# RF_Test_Board.net
KiCad netlist of a schematic drawn in EAGLE
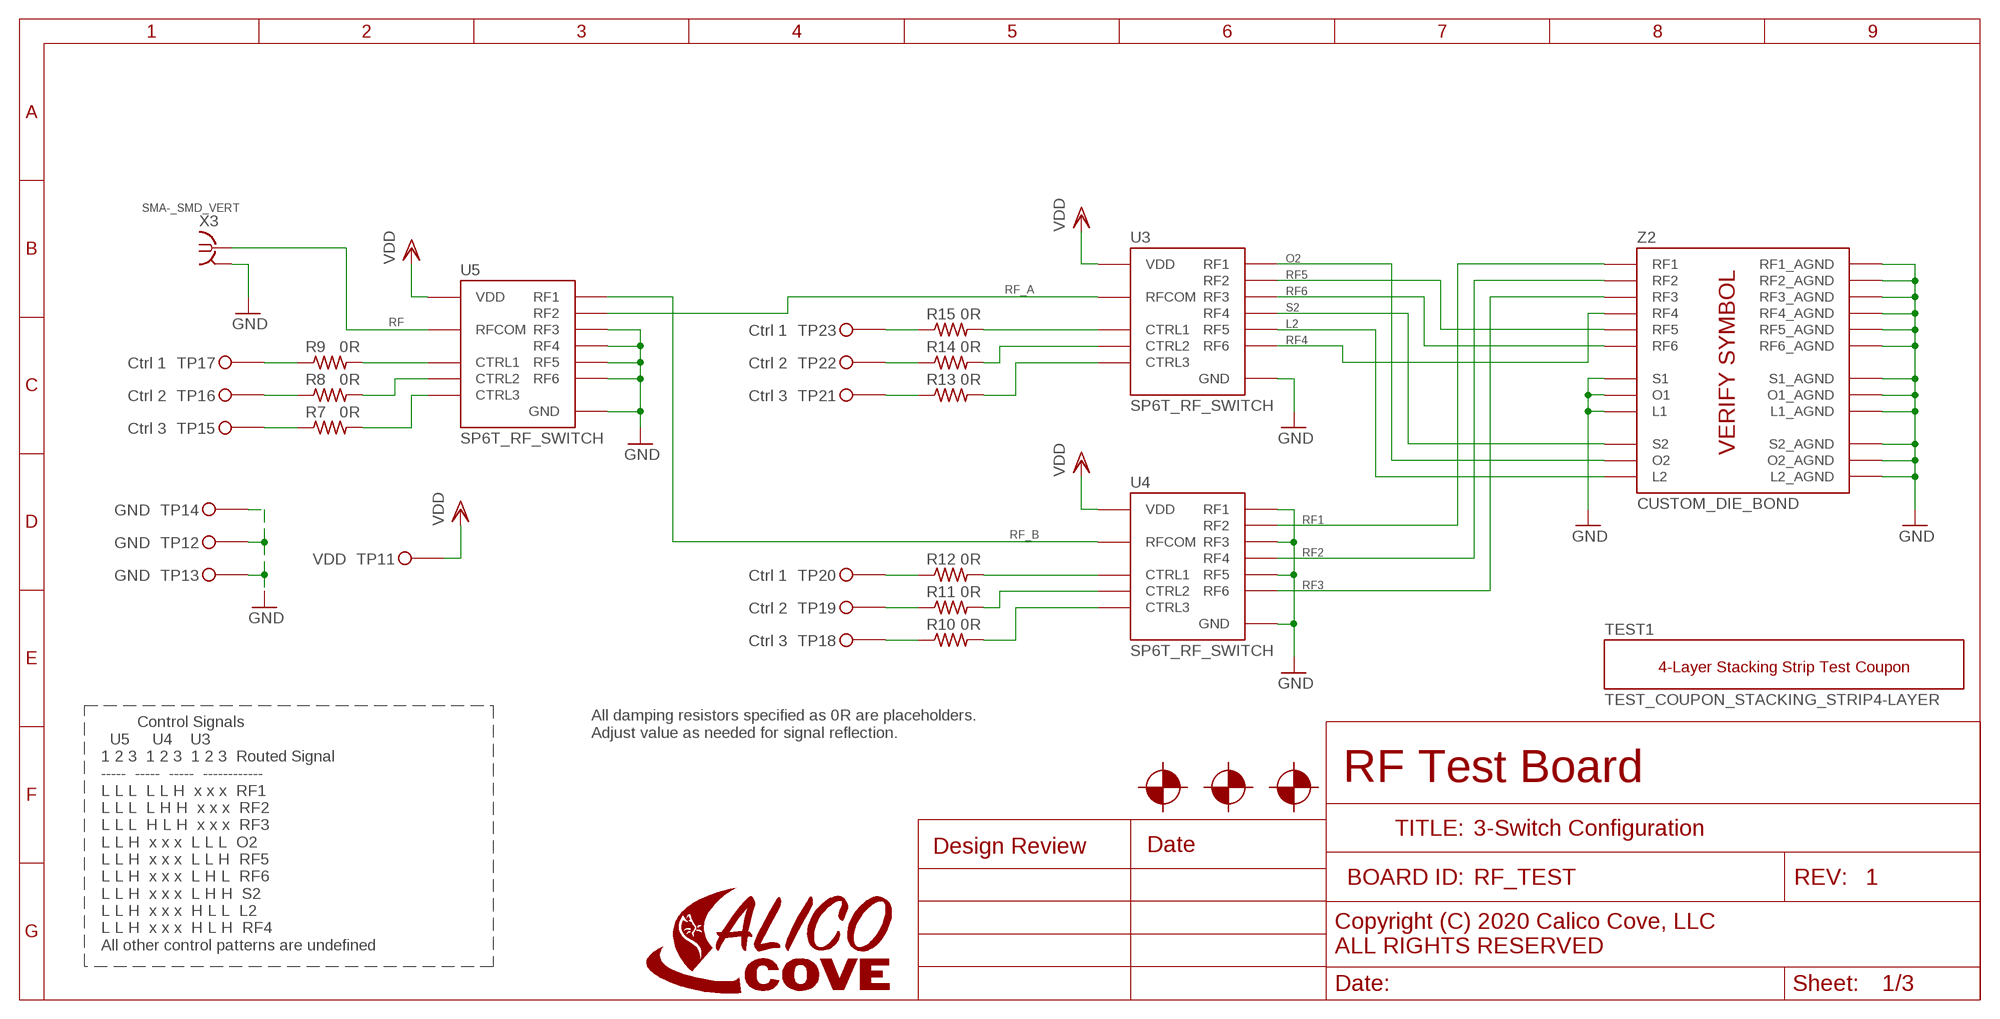
[diagram p0: schematic, sheet 1]
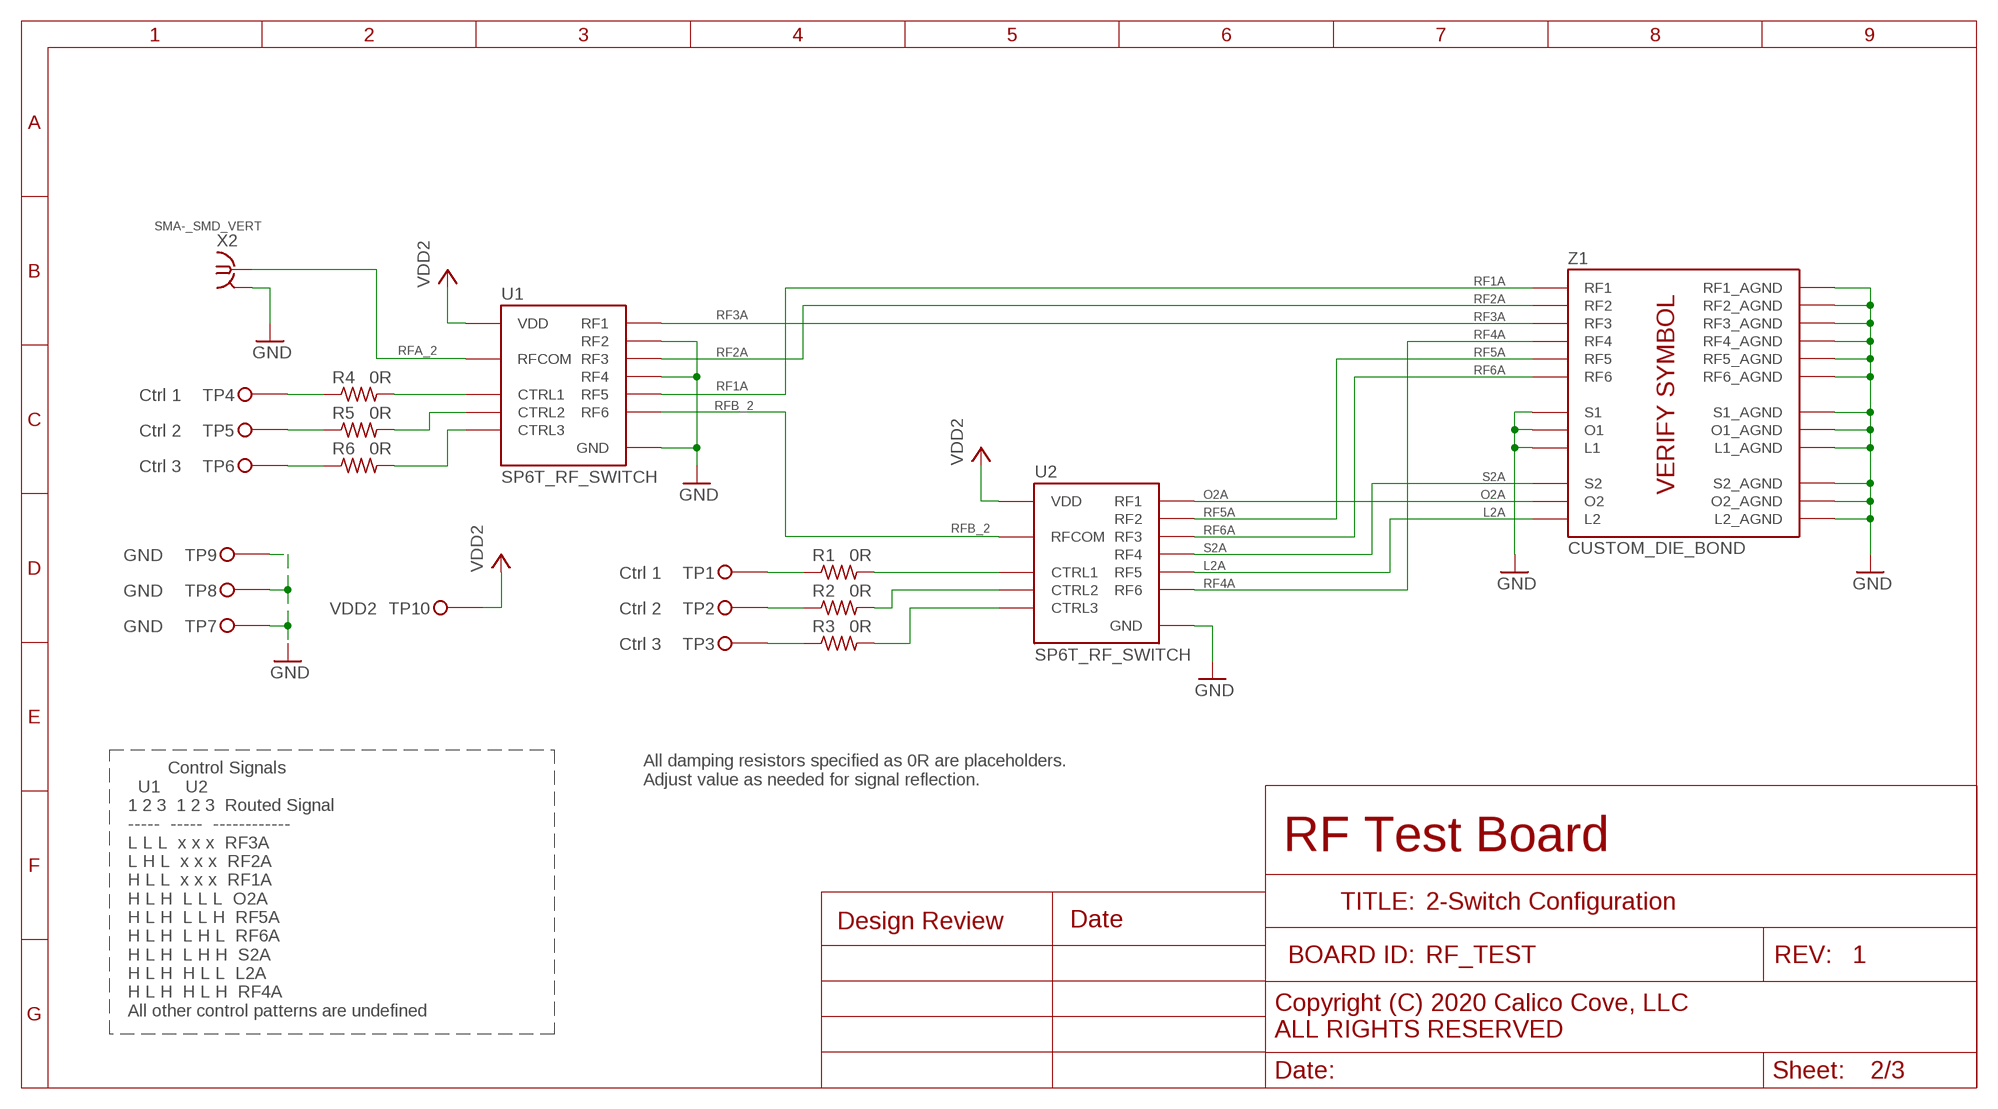
[diagram p1: schematic, sheet 2]
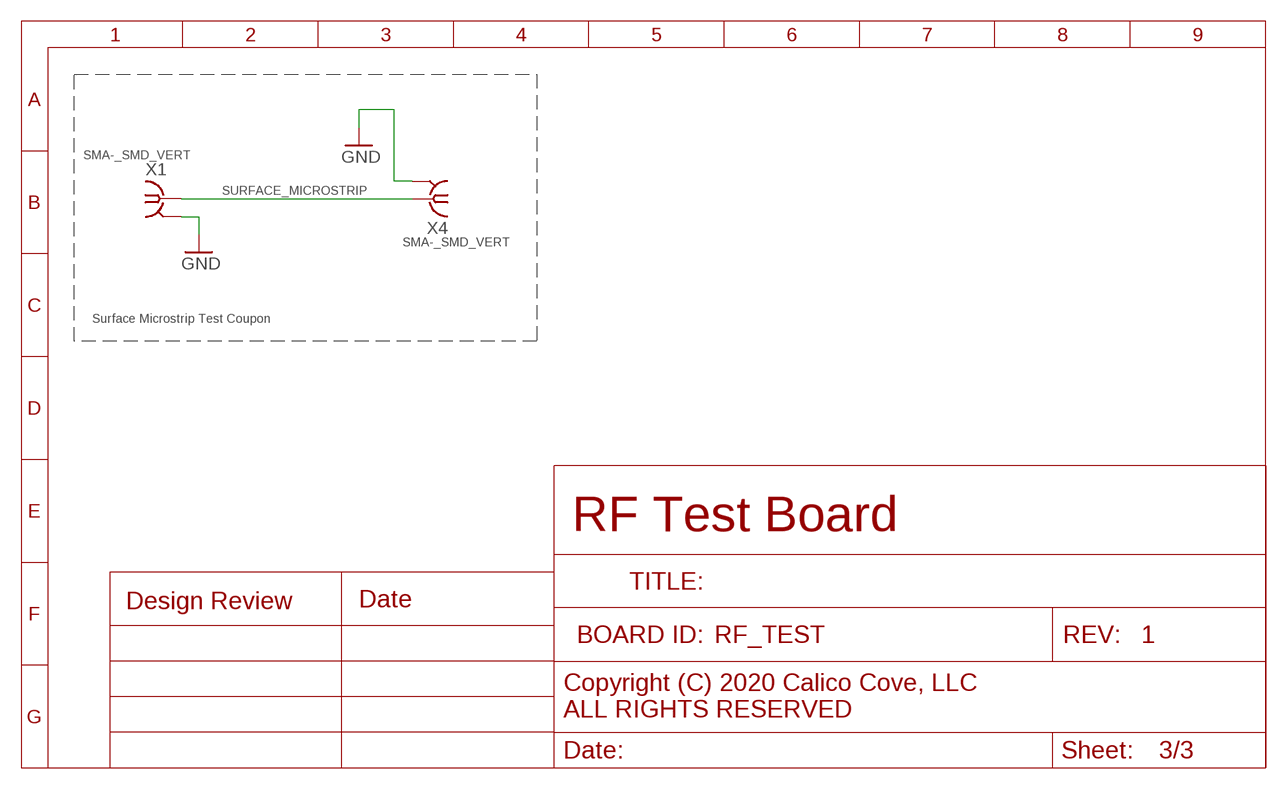
[diagram p2: schematic, sheet 3]

(export (version "E")
  (design (tool "Eeschema 10.0.6"))
  (components
    (comp (ref "X1")
      (value "SMA-_SMD_VERT")
      (footprint "eagle-import:LINX_SMD")
      (fields (field (name "MFG") "Linx Technologies, Inc.") (field (name "MPN") "CONSMA001-SMD-G"))
      (libsource (lib "eagle-import") (part "SMA-_SMD_VERT"))
    )
    (comp (ref "X4")
      (value "SMA-_SMD_VERT")
      (footprint "eagle-import:LINX_SMD")
      (fields (field (name "MFG") "Linx Technologies, Inc.") (field (name "MPN") "CONSMA001-SMD-G"))
      (libsource (lib "eagle-import") (part "SMA-_SMD_VERT"))
    )
    (comp (ref "R1")
      (value "0R")
      (footprint "eagle-import:0603")
      (libsource (lib "eagle-import") (part "RESISTOR0603"))
    )
    (comp (ref "R2")
      (value "0R")
      (footprint "eagle-import:0603")
      (libsource (lib "eagle-import") (part "RESISTOR0603"))
    )
    (comp (ref "R3")
      (value "0R")
      (footprint "eagle-import:0603")
      (libsource (lib "eagle-import") (part "RESISTOR0603"))
    )
    (comp (ref "R4")
      (value "0R")
      (footprint "eagle-import:0603")
      (libsource (lib "eagle-import") (part "RESISTOR0603"))
    )
    (comp (ref "R5")
      (value "0R")
      (footprint "eagle-import:0603")
      (libsource (lib "eagle-import") (part "RESISTOR0603"))
    )
    (comp (ref "R6")
      (value "0R")
      (footprint "eagle-import:0603")
      (libsource (lib "eagle-import") (part "RESISTOR0603"))
    )
    (comp (ref "TP1")
      (value "Ctrl 1")
      (footprint "eagle-import:TEST_POINT_TH")
      (libsource (lib "eagle-import") (part "TEST_POINT_TH"))
    )
    (comp (ref "TP2")
      (value "Ctrl 2")
      (footprint "eagle-import:TEST_POINT_TH")
      (libsource (lib "eagle-import") (part "TEST_POINT_TH"))
    )
    (comp (ref "TP3")
      (value "Ctrl 3")
      (footprint "eagle-import:TEST_POINT_TH")
      (libsource (lib "eagle-import") (part "TEST_POINT_TH"))
    )
    (comp (ref "TP4")
      (value "Ctrl 1")
      (footprint "eagle-import:TEST_POINT_TH")
      (libsource (lib "eagle-import") (part "TEST_POINT_TH"))
    )
    (comp (ref "TP5")
      (value "Ctrl 2")
      (footprint "eagle-import:TEST_POINT_TH")
      (libsource (lib "eagle-import") (part "TEST_POINT_TH"))
    )
    (comp (ref "TP6")
      (value "Ctrl 3")
      (footprint "eagle-import:TEST_POINT_TH")
      (libsource (lib "eagle-import") (part "TEST_POINT_TH"))
    )
    (comp (ref "TP7")
      (value "GND")
      (footprint "eagle-import:TEST_POINT_TH")
      (libsource (lib "eagle-import") (part "TEST_POINT_TH"))
    )
    (comp (ref "TP8")
      (value "GND")
      (footprint "eagle-import:TEST_POINT_TH")
      (libsource (lib "eagle-import") (part "TEST_POINT_TH"))
    )
    (comp (ref "TP9")
      (value "GND")
      (footprint "eagle-import:TEST_POINT_TH")
      (libsource (lib "eagle-import") (part "TEST_POINT_TH"))
    )
    (comp (ref "TP10")
      (value "VDD2")
      (footprint "eagle-import:TEST_POINT_TH")
      (libsource (lib "eagle-import") (part "TEST_POINT_TH"))
    )
    (comp (ref "U1")
      (value "SP6T_RF_SWITCH")
      (footprint "eagle-import:MT1817")
      (libsource (lib "eagle-import") (part "SP6T_RF_SWITCH"))
    )
    (comp (ref "U2")
      (value "SP6T_RF_SWITCH")
      (footprint "eagle-import:MT1817")
      (libsource (lib "eagle-import") (part "SP6T_RF_SWITCH"))
    )
    (comp (ref "X2")
      (value "SMA-_SMD_VERT")
      (footprint "eagle-import:LINX_SMD")
      (fields (field (name "MFG") "Linx Technologies, Inc.") (field (name "MPN") "CONSMA001-SMD-G"))
      (libsource (lib "eagle-import") (part "SMA-_SMD_VERT"))
    )
    (comp (ref "Z1")
      (value "CUSTOM_DIE_BOND")
      (footprint "eagle-import:CUSTOM_IC_DIE_BOND")
      (libsource (lib "eagle-import") (part "CUSTOM_DIE_BOND"))
    )
    (comp (ref "DOCBLOCK1")
      (value "DOCBLOCK_REVIEW_2020")
      (footprint "eagle-import:DOCBLOCK")
      (libsource (lib "eagle-import") (part "DOCBLOCK_REVIEW_2020"))
    )
    (comp (ref "FID$1")
      (value "FIDUCIAL")
      (footprint "eagle-import:FIDUCIAL")
      (libsource (lib "eagle-import") (part "FIDUCIAL"))
    )
    (comp (ref "FID$2")
      (value "FIDUCIAL")
      (footprint "eagle-import:FIDUCIAL")
      (libsource (lib "eagle-import") (part "FIDUCIAL"))
    )
    (comp (ref "FID$3")
      (value "FIDUCIAL")
      (footprint "eagle-import:FIDUCIAL")
      (libsource (lib "eagle-import") (part "FIDUCIAL"))
    )
    (comp (ref "LOGO1")
      (value "LOGO_CC_SMALL")
      (footprint "eagle-import:CC_FULL_SMALL")
      (libsource (lib "eagle-import") (part "LOGO_CC_SMALL"))
    )
    (comp (ref "R7")
      (value "0R")
      (footprint "eagle-import:0603")
      (libsource (lib "eagle-import") (part "RESISTOR0603"))
    )
    (comp (ref "R8")
      (value "0R")
      (footprint "eagle-import:0603")
      (libsource (lib "eagle-import") (part "RESISTOR0603"))
    )
    (comp (ref "R9")
      (value "0R")
      (footprint "eagle-import:0603")
      (libsource (lib "eagle-import") (part "RESISTOR0603"))
    )
    (comp (ref "R10")
      (value "0R")
      (footprint "eagle-import:0603")
      (libsource (lib "eagle-import") (part "RESISTOR0603"))
    )
    (comp (ref "R11")
      (value "0R")
      (footprint "eagle-import:0603")
      (libsource (lib "eagle-import") (part "RESISTOR0603"))
    )
    (comp (ref "R12")
      (value "0R")
      (footprint "eagle-import:0603")
      (libsource (lib "eagle-import") (part "RESISTOR0603"))
    )
    (comp (ref "R13")
      (value "0R")
      (footprint "eagle-import:0603")
      (libsource (lib "eagle-import") (part "RESISTOR0603"))
    )
    (comp (ref "R14")
      (value "0R")
      (footprint "eagle-import:0603")
      (libsource (lib "eagle-import") (part "RESISTOR0603"))
    )
    (comp (ref "R15")
      (value "0R")
      (footprint "eagle-import:0603")
      (libsource (lib "eagle-import") (part "RESISTOR0603"))
    )
    (comp (ref "TEST1")
      (value "TEST_COUPON_STACKING_STRIP4-LAYER")
      (footprint "eagle-import:TEST_COUPON_4-LAYER_STACKING_STRIP")
      (libsource (lib "eagle-import") (part "TEST_COUPON_STACKING_STRIP4-LAYER"))
    )
    (comp (ref "TP11")
      (value "VDD")
      (footprint "eagle-import:TEST_POINT_TH")
      (libsource (lib "eagle-import") (part "TEST_POINT_TH"))
    )
    (comp (ref "TP12")
      (value "GND")
      (footprint "eagle-import:TEST_POINT_TH")
      (libsource (lib "eagle-import") (part "TEST_POINT_TH"))
    )
    (comp (ref "TP13")
      (value "GND")
      (footprint "eagle-import:TEST_POINT_TH")
      (libsource (lib "eagle-import") (part "TEST_POINT_TH"))
    )
    (comp (ref "TP14")
      (value "GND")
      (footprint "eagle-import:TEST_POINT_TH")
      (libsource (lib "eagle-import") (part "TEST_POINT_TH"))
    )
    (comp (ref "TP15")
      (value "Ctrl 3")
      (footprint "eagle-import:TEST_POINT_TH")
      (libsource (lib "eagle-import") (part "TEST_POINT_TH"))
    )
    (comp (ref "TP16")
      (value "Ctrl 2")
      (footprint "eagle-import:TEST_POINT_TH")
      (libsource (lib "eagle-import") (part "TEST_POINT_TH"))
    )
    (comp (ref "TP17")
      (value "Ctrl 1")
      (footprint "eagle-import:TEST_POINT_TH")
      (libsource (lib "eagle-import") (part "TEST_POINT_TH"))
    )
    (comp (ref "TP18")
      (value "Ctrl 3")
      (footprint "eagle-import:TEST_POINT_TH")
      (libsource (lib "eagle-import") (part "TEST_POINT_TH"))
    )
    (comp (ref "TP19")
      (value "Ctrl 2")
      (footprint "eagle-import:TEST_POINT_TH")
      (libsource (lib "eagle-import") (part "TEST_POINT_TH"))
    )
    (comp (ref "TP20")
      (value "Ctrl 1")
      (footprint "eagle-import:TEST_POINT_TH")
      (libsource (lib "eagle-import") (part "TEST_POINT_TH"))
    )
    (comp (ref "TP21")
      (value "Ctrl 3")
      (footprint "eagle-import:TEST_POINT_TH")
      (libsource (lib "eagle-import") (part "TEST_POINT_TH"))
    )
    (comp (ref "TP22")
      (value "Ctrl 2")
      (footprint "eagle-import:TEST_POINT_TH")
      (libsource (lib "eagle-import") (part "TEST_POINT_TH"))
    )
    (comp (ref "TP23")
      (value "Ctrl 1")
      (footprint "eagle-import:TEST_POINT_TH")
      (libsource (lib "eagle-import") (part "TEST_POINT_TH"))
    )
    (comp (ref "U3")
      (value "SP6T_RF_SWITCH")
      (footprint "eagle-import:MT1817")
      (libsource (lib "eagle-import") (part "SP6T_RF_SWITCH"))
    )
    (comp (ref "U4")
      (value "SP6T_RF_SWITCH")
      (footprint "eagle-import:MT1817")
      (libsource (lib "eagle-import") (part "SP6T_RF_SWITCH"))
    )
    (comp (ref "U5")
      (value "SP6T_RF_SWITCH")
      (footprint "eagle-import:MT1817")
      (libsource (lib "eagle-import") (part "SP6T_RF_SWITCH"))
    )
    (comp (ref "X3")
      (value "SMA-_SMD_VERT")
      (footprint "eagle-import:LINX_SMD")
      (fields (field (name "MFG") "Linx Technologies, Inc.") (field (name "MPN") "CONSMA001-SMD-G"))
      (libsource (lib "eagle-import") (part "SMA-_SMD_VERT"))
    )
    (comp (ref "Z2")
      (value "CUSTOM_DIE_BOND")
      (footprint "eagle-import:CUSTOM_IC_DIE_BOND")
      (libsource (lib "eagle-import") (part "CUSTOM_DIE_BOND"))
    )
  )
  (nets
    (net (code "1") (name "GND") (class "Default")
      (node (ref "TP12") (pin "P$1") (pinfunction "P$1_P$1") (pintype "passive"))
      (node (ref "TP13") (pin "P$1") (pinfunction "P$1_P$1") (pintype "passive"))
      (node (ref "TP14") (pin "P$1") (pinfunction "P$1_P$1") (pintype "passive"))
      (node (ref "TP7") (pin "P$1") (pinfunction "P$1_P$1") (pintype "passive"))
      (node (ref "TP8") (pin "P$1") (pinfunction "P$1_P$1") (pintype "passive"))
      (node (ref "TP9") (pin "P$1") (pinfunction "P$1_P$1") (pintype "passive"))
      (node (ref "U1") (pin "10") (pinfunction "RF4_10") (pintype "passive"))
      (node (ref "U1") (pin "9") (pinfunction "RF2_9") (pintype "passive"))
      (node (ref "U1") (pin "PAD") (pinfunction "GND_PAD") (pintype "power_in"))
      (node (ref "U1") (pin "PAD_VIA") (pinfunction "GND_PAD_VIA") (pintype "power_in"))
      (node (ref "U2") (pin "PAD") (pinfunction "GND_PAD") (pintype "power_in"))
      (node (ref "U2") (pin "PAD_VIA") (pinfunction "GND_PAD_VIA") (pintype "power_in"))
      (node (ref "U3") (pin "PAD") (pinfunction "GND_PAD") (pintype "power_in"))
      (node (ref "U3") (pin "PAD_VIA") (pinfunction "GND_PAD_VIA") (pintype "power_in"))
      (node (ref "U4") (pin "1") (pinfunction "RF5_1") (pintype "passive"))
      (node (ref "U4") (pin "2") (pinfunction "RF3_2") (pintype "passive"))
      (node (ref "U4") (pin "3") (pinfunction "RF1_3") (pintype "passive"))
      (node (ref "U4") (pin "PAD") (pinfunction "GND_PAD") (pintype "power_in"))
      (node (ref "U4") (pin "PAD_VIA") (pinfunction "GND_PAD_VIA") (pintype "power_in"))
      (node (ref "U5") (pin "1") (pinfunction "RF5_1") (pintype "passive"))
      (node (ref "U5") (pin "10") (pinfunction "RF4_10") (pintype "passive"))
      (node (ref "U5") (pin "11") (pinfunction "RF6_11") (pintype "passive"))
      (node (ref "U5") (pin "2") (pinfunction "RF3_2") (pintype "passive"))
      (node (ref "U5") (pin "PAD") (pinfunction "GND_PAD") (pintype "power_in"))
      (node (ref "U5") (pin "PAD_VIA") (pinfunction "GND_PAD_VIA") (pintype "power_in"))
      (node (ref "X1") (pin "GND1") (pinfunction "SHIELD_GND1") (pintype "passive"))
      (node (ref "X1") (pin "GND2") (pinfunction "SHIELD_GND2") (pintype "passive"))
      (node (ref "X2") (pin "GND1") (pinfunction "SHIELD_GND1") (pintype "passive"))
      (node (ref "X2") (pin "GND2") (pinfunction "SHIELD_GND2") (pintype "passive"))
      (node (ref "X3") (pin "GND1") (pinfunction "SHIELD_GND1") (pintype "passive"))
      (node (ref "X3") (pin "GND2") (pinfunction "SHIELD_GND2") (pintype "passive"))
      (node (ref "X4") (pin "GND1") (pinfunction "SHIELD_GND1") (pintype "passive"))
      (node (ref "X4") (pin "GND2") (pinfunction "SHIELD_GND2") (pintype "passive"))
      (node (ref "Z1") (pin "L1") (pinfunction "L1_L1") (pintype "passive"))
      (node (ref "Z1") (pin "L1_GND1") (pinfunction "L1_AGND_L1_GND1") (pintype "power_in"))
      (node (ref "Z1") (pin "L1_GND2") (pinfunction "L1_AGND_L1_GND2") (pintype "power_in"))
      (node (ref "Z1") (pin "L2_GND1") (pinfunction "L2_AGND_L2_GND1") (pintype "power_in"))
      (node (ref "Z1") (pin "L2_GND2") (pinfunction "L2_AGND_L2_GND2") (pintype "power_in"))
      (node (ref "Z1") (pin "O1") (pinfunction "O1_O1") (pintype "passive"))
      (node (ref "Z1") (pin "O1_GND1") (pinfunction "O1_AGND_O1_GND1") (pintype "power_in"))
      (node (ref "Z1") (pin "O1_GND2") (pinfunction "O1_AGND_O1_GND2") (pintype "power_in"))
      (node (ref "Z1") (pin "O2_GND1") (pinfunction "O2_AGND_O2_GND1") (pintype "power_in"))
      (node (ref "Z1") (pin "O2_GND2") (pinfunction "O2_AGND_O2_GND2") (pintype "power_in"))
      (node (ref "Z1") (pin "RF1_GND1") (pinfunction "RF1_AGND_RF1_GND1") (pintype "power_in"))
      (node (ref "Z1") (pin "RF1_GND2") (pinfunction "RF1_AGND_RF1_GND2") (pintype "power_in"))
      (node (ref "Z1") (pin "RF2_GND1") (pinfunction "RF2_AGND_RF2_GND1") (pintype "power_in"))
      (node (ref "Z1") (pin "RF2_GND2") (pinfunction "RF2_AGND_RF2_GND2") (pintype "power_in"))
      (node (ref "Z1") (pin "RF3_GND1") (pinfunction "RF3_AGND_RF3_GND1") (pintype "power_in"))
      (node (ref "Z1") (pin "RF3_GND2") (pinfunction "RF3_AGND_RF3_GND2") (pintype "power_in"))
      (node (ref "Z1") (pin "RF4_GND1") (pinfunction "RF4_AGND_RF4_GND1") (pintype "power_in"))
      (node (ref "Z1") (pin "RF4_GND2") (pinfunction "RF4_AGND_RF4_GND2") (pintype "power_in"))
      (node (ref "Z1") (pin "RF5_GND1") (pinfunction "RF5_AGND_RF5_GND1") (pintype "power_in"))
      (node (ref "Z1") (pin "RF5_GND2") (pinfunction "RF5_AGND_RF5_GND2") (pintype "power_in"))
      (node (ref "Z1") (pin "RF6_GND1") (pinfunction "RF6_AGND_RF6_GND1") (pintype "power_in"))
      (node (ref "Z1") (pin "RG6_GND2") (pinfunction "RF6_AGND_RG6_GND2") (pintype "power_in"))
      (node (ref "Z1") (pin "S1") (pinfunction "S1_S1") (pintype "passive"))
      (node (ref "Z1") (pin "S1_GND1") (pinfunction "S1_AGND_S1_GND1") (pintype "power_in"))
      (node (ref "Z1") (pin "S1_GND2") (pinfunction "S1_AGND_S1_GND2") (pintype "power_in"))
      (node (ref "Z1") (pin "S2_GND1") (pinfunction "S2_AGND_S2_GND1") (pintype "power_in"))
      (node (ref "Z1") (pin "S2_GND2") (pinfunction "S2_AGND_S2_GND2") (pintype "power_in"))
      (node (ref "Z2") (pin "L1") (pinfunction "L1_L1") (pintype "passive"))
      (node (ref "Z2") (pin "L1_GND1") (pinfunction "L1_AGND_L1_GND1") (pintype "power_in"))
      (node (ref "Z2") (pin "L1_GND2") (pinfunction "L1_AGND_L1_GND2") (pintype "power_in"))
      (node (ref "Z2") (pin "L2_GND1") (pinfunction "L2_AGND_L2_GND1") (pintype "power_in"))
      (node (ref "Z2") (pin "L2_GND2") (pinfunction "L2_AGND_L2_GND2") (pintype "power_in"))
      (node (ref "Z2") (pin "O1") (pinfunction "O1_O1") (pintype "passive"))
      (node (ref "Z2") (pin "O1_GND1") (pinfunction "O1_AGND_O1_GND1") (pintype "power_in"))
      (node (ref "Z2") (pin "O1_GND2") (pinfunction "O1_AGND_O1_GND2") (pintype "power_in"))
      (node (ref "Z2") (pin "O2_GND1") (pinfunction "O2_AGND_O2_GND1") (pintype "power_in"))
      (node (ref "Z2") (pin "O2_GND2") (pinfunction "O2_AGND_O2_GND2") (pintype "power_in"))
      (node (ref "Z2") (pin "RF1_GND1") (pinfunction "RF1_AGND_RF1_GND1") (pintype "power_in"))
      (node (ref "Z2") (pin "RF1_GND2") (pinfunction "RF1_AGND_RF1_GND2") (pintype "power_in"))
      (node (ref "Z2") (pin "RF2_GND1") (pinfunction "RF2_AGND_RF2_GND1") (pintype "power_in"))
      (node (ref "Z2") (pin "RF2_GND2") (pinfunction "RF2_AGND_RF2_GND2") (pintype "power_in"))
      (node (ref "Z2") (pin "RF3_GND1") (pinfunction "RF3_AGND_RF3_GND1") (pintype "power_in"))
      (node (ref "Z2") (pin "RF3_GND2") (pinfunction "RF3_AGND_RF3_GND2") (pintype "power_in"))
      (node (ref "Z2") (pin "RF4_GND1") (pinfunction "RF4_AGND_RF4_GND1") (pintype "power_in"))
      (node (ref "Z2") (pin "RF4_GND2") (pinfunction "RF4_AGND_RF4_GND2") (pintype "power_in"))
      (node (ref "Z2") (pin "RF5_GND1") (pinfunction "RF5_AGND_RF5_GND1") (pintype "power_in"))
      (node (ref "Z2") (pin "RF5_GND2") (pinfunction "RF5_AGND_RF5_GND2") (pintype "power_in"))
      (node (ref "Z2") (pin "RF6_GND1") (pinfunction "RF6_AGND_RF6_GND1") (pintype "power_in"))
      (node (ref "Z2") (pin "RG6_GND2") (pinfunction "RF6_AGND_RG6_GND2") (pintype "power_in"))
      (node (ref "Z2") (pin "S1") (pinfunction "S1_S1") (pintype "passive"))
      (node (ref "Z2") (pin "S1_GND1") (pinfunction "S1_AGND_S1_GND1") (pintype "power_in"))
      (node (ref "Z2") (pin "S1_GND2") (pinfunction "S1_AGND_S1_GND2") (pintype "power_in"))
      (node (ref "Z2") (pin "S2_GND1") (pinfunction "S2_AGND_S2_GND1") (pintype "power_in"))
      (node (ref "Z2") (pin "S2_GND2") (pinfunction "S2_AGND_S2_GND2") (pintype "power_in"))
    )
    (net (code "2") (name "L2") (class "Default")
      (node (ref "U3") (pin "1") (pinfunction "RF5_1") (pintype "passive"))
      (node (ref "Z2") (pin "L2") (pinfunction "L2_L2") (pintype "passive"))
    )
    (net (code "3") (name "L2A") (class "Default")
      (node (ref "U2") (pin "1") (pinfunction "RF5_1") (pintype "passive"))
      (node (ref "Z1") (pin "L2") (pinfunction "L2_L2") (pintype "passive"))
    )
    (net (code "4") (name "Net-(R1-1)") (class "Default")
      (node (ref "R1") (pin "P$1") (pinfunction "1_P$1") (pintype "passive"))
      (node (ref "TP1") (pin "P$1") (pinfunction "P$1_P$1") (pintype "passive"))
    )
    (net (code "5") (name "Net-(R1-2)") (class "Default")
      (node (ref "R1") (pin "P$2") (pinfunction "2_P$2") (pintype "passive"))
      (node (ref "U2") (pin "7") (pinfunction "CTRL1_7") (pintype "input"))
    )
    (net (code "6") (name "Net-(R2-1)") (class "Default")
      (node (ref "R2") (pin "P$1") (pinfunction "1_P$1") (pintype "passive"))
      (node (ref "TP2") (pin "P$1") (pinfunction "P$1_P$1") (pintype "passive"))
    )
    (net (code "7") (name "Net-(R2-2)") (class "Default")
      (node (ref "R2") (pin "P$2") (pinfunction "2_P$2") (pintype "passive"))
      (node (ref "U2") (pin "6") (pinfunction "CTRL2_6") (pintype "input"))
    )
    (net (code "8") (name "Net-(R3-1)") (class "Default")
      (node (ref "R3") (pin "P$1") (pinfunction "1_P$1") (pintype "passive"))
      (node (ref "TP3") (pin "P$1") (pinfunction "P$1_P$1") (pintype "passive"))
    )
    (net (code "9") (name "Net-(R3-2)") (class "Default")
      (node (ref "R3") (pin "P$2") (pinfunction "2_P$2") (pintype "passive"))
      (node (ref "U2") (pin "5") (pinfunction "CTRL3_5") (pintype "input"))
    )
    (net (code "10") (name "Net-(R4-1)") (class "Default")
      (node (ref "R4") (pin "P$1") (pinfunction "1_P$1") (pintype "passive"))
      (node (ref "TP4") (pin "P$1") (pinfunction "P$1_P$1") (pintype "passive"))
    )
    (net (code "11") (name "Net-(R4-2)") (class "Default")
      (node (ref "R4") (pin "P$2") (pinfunction "2_P$2") (pintype "passive"))
      (node (ref "U1") (pin "7") (pinfunction "CTRL1_7") (pintype "input"))
    )
    (net (code "12") (name "Net-(R5-1)") (class "Default")
      (node (ref "R5") (pin "P$1") (pinfunction "1_P$1") (pintype "passive"))
      (node (ref "TP5") (pin "P$1") (pinfunction "P$1_P$1") (pintype "passive"))
    )
    (net (code "13") (name "Net-(R5-2)") (class "Default")
      (node (ref "R5") (pin "P$2") (pinfunction "2_P$2") (pintype "passive"))
      (node (ref "U1") (pin "6") (pinfunction "CTRL2_6") (pintype "input"))
    )
    (net (code "14") (name "Net-(R6-1)") (class "Default")
      (node (ref "R6") (pin "P$1") (pinfunction "1_P$1") (pintype "passive"))
      (node (ref "TP6") (pin "P$1") (pinfunction "P$1_P$1") (pintype "passive"))
    )
    (net (code "15") (name "Net-(R6-2)") (class "Default")
      (node (ref "R6") (pin "P$2") (pinfunction "2_P$2") (pintype "passive"))
      (node (ref "U1") (pin "5") (pinfunction "CTRL3_5") (pintype "input"))
    )
    (net (code "16") (name "Net-(R7-1)") (class "Default")
      (node (ref "R7") (pin "P$1") (pinfunction "1_P$1") (pintype "passive"))
      (node (ref "TP15") (pin "P$1") (pinfunction "P$1_P$1") (pintype "passive"))
    )
    (net (code "17") (name "Net-(R7-2)") (class "Default")
      (node (ref "R7") (pin "P$2") (pinfunction "2_P$2") (pintype "passive"))
      (node (ref "U5") (pin "5") (pinfunction "CTRL3_5") (pintype "input"))
    )
    (net (code "18") (name "Net-(R8-1)") (class "Default")
      (node (ref "R8") (pin "P$1") (pinfunction "1_P$1") (pintype "passive"))
      (node (ref "TP16") (pin "P$1") (pinfunction "P$1_P$1") (pintype "passive"))
    )
    (net (code "19") (name "Net-(R8-2)") (class "Default")
      (node (ref "R8") (pin "P$2") (pinfunction "2_P$2") (pintype "passive"))
      (node (ref "U5") (pin "6") (pinfunction "CTRL2_6") (pintype "input"))
    )
    (net (code "20") (name "Net-(R9-1)") (class "Default")
      (node (ref "R9") (pin "P$1") (pinfunction "1_P$1") (pintype "passive"))
      (node (ref "TP17") (pin "P$1") (pinfunction "P$1_P$1") (pintype "passive"))
    )
    (net (code "21") (name "Net-(R9-2)") (class "Default")
      (node (ref "R9") (pin "P$2") (pinfunction "2_P$2") (pintype "passive"))
      (node (ref "U5") (pin "7") (pinfunction "CTRL1_7") (pintype "input"))
    )
    (net (code "22") (name "Net-(R10-1)") (class "Default")
      (node (ref "R10") (pin "P$1") (pinfunction "1_P$1") (pintype "passive"))
      (node (ref "TP18") (pin "P$1") (pinfunction "P$1_P$1") (pintype "passive"))
    )
    (net (code "23") (name "Net-(R10-2)") (class "Default")
      (node (ref "R10") (pin "P$2") (pinfunction "2_P$2") (pintype "passive"))
      (node (ref "U4") (pin "5") (pinfunction "CTRL3_5") (pintype "input"))
    )
    (net (code "24") (name "Net-(R11-1)") (class "Default")
      (node (ref "R11") (pin "P$1") (pinfunction "1_P$1") (pintype "passive"))
      (node (ref "TP19") (pin "P$1") (pinfunction "P$1_P$1") (pintype "passive"))
    )
    (net (code "25") (name "Net-(R11-2)") (class "Default")
      (node (ref "R11") (pin "P$2") (pinfunction "2_P$2") (pintype "passive"))
      (node (ref "U4") (pin "6") (pinfunction "CTRL2_6") (pintype "input"))
    )
    (net (code "26") (name "Net-(R12-1)") (class "Default")
      (node (ref "R12") (pin "P$1") (pinfunction "1_P$1") (pintype "passive"))
      (node (ref "TP20") (pin "P$1") (pinfunction "P$1_P$1") (pintype "passive"))
    )
    (net (code "27") (name "Net-(R12-2)") (class "Default")
      (node (ref "R12") (pin "P$2") (pinfunction "2_P$2") (pintype "passive"))
      (node (ref "U4") (pin "7") (pinfunction "CTRL1_7") (pintype "input"))
    )
    (net (code "28") (name "Net-(R13-1)") (class "Default")
      (node (ref "R13") (pin "P$1") (pinfunction "1_P$1") (pintype "passive"))
      (node (ref "TP21") (pin "P$1") (pinfunction "P$1_P$1") (pintype "passive"))
    )
    (net (code "29") (name "Net-(R13-2)") (class "Default")
      (node (ref "R13") (pin "P$2") (pinfunction "2_P$2") (pintype "passive"))
      (node (ref "U3") (pin "5") (pinfunction "CTRL3_5") (pintype "input"))
    )
    (net (code "30") (name "Net-(R14-1)") (class "Default")
      (node (ref "R14") (pin "P$1") (pinfunction "1_P$1") (pintype "passive"))
      (node (ref "TP22") (pin "P$1") (pinfunction "P$1_P$1") (pintype "passive"))
    )
    (net (code "31") (name "Net-(R14-2)") (class "Default")
      (node (ref "R14") (pin "P$2") (pinfunction "2_P$2") (pintype "passive"))
      (node (ref "U3") (pin "6") (pinfunction "CTRL2_6") (pintype "input"))
    )
    (net (code "32") (name "Net-(R15-1)") (class "Default")
      (node (ref "R15") (pin "P$1") (pinfunction "1_P$1") (pintype "passive"))
      (node (ref "TP23") (pin "P$1") (pinfunction "P$1_P$1") (pintype "passive"))
    )
    (net (code "33") (name "Net-(R15-2)") (class "Default")
      (node (ref "R15") (pin "P$2") (pinfunction "2_P$2") (pintype "passive"))
      (node (ref "U3") (pin "7") (pinfunction "CTRL1_7") (pintype "input"))
    )
    (net (code "34") (name "O2") (class "Default")
      (node (ref "U3") (pin "3") (pinfunction "RF1_3") (pintype "passive"))
      (node (ref "Z2") (pin "O2") (pinfunction "O2_O2") (pintype "passive"))
    )
    (net (code "35") (name "O2A") (class "Default")
      (node (ref "U2") (pin "3") (pinfunction "RF1_3") (pintype "passive"))
      (node (ref "Z1") (pin "O2") (pinfunction "O2_O2") (pintype "passive"))
    )
    (net (code "36") (name "RF") (class "Default")
      (node (ref "U5") (pin "13") (pinfunction "RFCOM_13") (pintype "passive"))
      (node (ref "X3") (pin "1") (pinfunction "1_1") (pintype "passive"))
    )
    (net (code "37") (name "RF1") (class "Default")
      (node (ref "U4") (pin "9") (pinfunction "RF2_9") (pintype "passive"))
      (node (ref "Z2") (pin "RF1") (pinfunction "RF1_RF1") (pintype "passive"))
    )
    (net (code "38") (name "RF1A") (class "Default")
      (node (ref "U1") (pin "1") (pinfunction "RF5_1") (pintype "passive"))
      (node (ref "Z1") (pin "RF1") (pinfunction "RF1_RF1") (pintype "passive"))
    )
    (net (code "39") (name "RF2") (class "Default")
      (node (ref "U4") (pin "10") (pinfunction "RF4_10") (pintype "passive"))
      (node (ref "Z2") (pin "RF2") (pinfunction "RF2_RF2") (pintype "passive"))
    )
    (net (code "40") (name "RF2A") (class "Default")
      (node (ref "U1") (pin "2") (pinfunction "RF3_2") (pintype "passive"))
      (node (ref "Z1") (pin "RF2") (pinfunction "RF2_RF2") (pintype "passive"))
    )
    (net (code "41") (name "RF3") (class "Default")
      (node (ref "U4") (pin "11") (pinfunction "RF6_11") (pintype "passive"))
      (node (ref "Z2") (pin "RF3") (pinfunction "RF3_RF3") (pintype "passive"))
    )
    (net (code "42") (name "RF3A") (class "Default")
      (node (ref "U1") (pin "3") (pinfunction "RF1_3") (pintype "passive"))
      (node (ref "Z1") (pin "RF3") (pinfunction "RF3_RF3") (pintype "passive"))
    )
    (net (code "43") (name "RF4") (class "Default")
      (node (ref "U3") (pin "11") (pinfunction "RF6_11") (pintype "passive"))
      (node (ref "Z2") (pin "RF4") (pinfunction "RF4_RF4") (pintype "passive"))
    )
    (net (code "44") (name "RF4A") (class "Default")
      (node (ref "U2") (pin "11") (pinfunction "RF6_11") (pintype "passive"))
      (node (ref "Z1") (pin "RF4") (pinfunction "RF4_RF4") (pintype "passive"))
    )
    (net (code "45") (name "RF5") (class "Default")
      (node (ref "U3") (pin "9") (pinfunction "RF2_9") (pintype "passive"))
      (node (ref "Z2") (pin "RF5") (pinfunction "RF5_RF5") (pintype "passive"))
    )
    (net (code "46") (name "RF5A") (class "Default")
      (node (ref "U2") (pin "9") (pinfunction "RF2_9") (pintype "passive"))
      (node (ref "Z1") (pin "RF5") (pinfunction "RF5_RF5") (pintype "passive"))
    )
    (net (code "47") (name "RF6") (class "Default")
      (node (ref "U3") (pin "2") (pinfunction "RF3_2") (pintype "passive"))
      (node (ref "Z2") (pin "RF6") (pinfunction "RF6_RF6") (pintype "passive"))
    )
    (net (code "48") (name "RF6A") (class "Default")
      (node (ref "U2") (pin "2") (pinfunction "RF3_2") (pintype "passive"))
      (node (ref "Z1") (pin "RF6") (pinfunction "RF6_RF6") (pintype "passive"))
    )
    (net (code "49") (name "RFA_2") (class "Default")
      (node (ref "U1") (pin "13") (pinfunction "RFCOM_13") (pintype "passive"))
      (node (ref "X2") (pin "1") (pinfunction "1_1") (pintype "passive"))
    )
    (net (code "50") (name "RFB_2") (class "Default")
      (node (ref "U1") (pin "11") (pinfunction "RF6_11") (pintype "passive"))
      (node (ref "U2") (pin "13") (pinfunction "RFCOM_13") (pintype "passive"))
    )
    (net (code "51") (name "RF_A") (class "Default")
      (node (ref "U3") (pin "13") (pinfunction "RFCOM_13") (pintype "passive"))
      (node (ref "U5") (pin "9") (pinfunction "RF2_9") (pintype "passive"))
    )
    (net (code "52") (name "RF_B") (class "Default")
      (node (ref "U4") (pin "13") (pinfunction "RFCOM_13") (pintype "passive"))
      (node (ref "U5") (pin "3") (pinfunction "RF1_3") (pintype "passive"))
    )
    (net (code "53") (name "S2") (class "Default")
      (node (ref "U3") (pin "10") (pinfunction "RF4_10") (pintype "passive"))
      (node (ref "Z2") (pin "S2") (pinfunction "S2_S2") (pintype "passive"))
    )
    (net (code "54") (name "S2A") (class "Default")
      (node (ref "U2") (pin "10") (pinfunction "RF4_10") (pintype "passive"))
      (node (ref "Z1") (pin "S2") (pinfunction "S2_S2") (pintype "passive"))
    )
    (net (code "55") (name "SURFACE_MICROSTRIP") (class "Default")
      (node (ref "X1") (pin "1") (pinfunction "1_1") (pintype "passive"))
      (node (ref "X4") (pin "1") (pinfunction "1_1") (pintype "passive"))
    )
    (net (code "56") (name "VDD") (class "Default")
      (node (ref "TP11") (pin "P$1") (pinfunction "P$1_P$1") (pintype "passive"))
      (node (ref "U3") (pin "4") (pinfunction "VDD_4") (pintype "power_in"))
      (node (ref "U4") (pin "4") (pinfunction "VDD_4") (pintype "power_in"))
      (node (ref "U5") (pin "4") (pinfunction "VDD_4") (pintype "power_in"))
    )
    (net (code "57") (name "VDD2") (class "Default")
      (node (ref "TP10") (pin "P$1") (pinfunction "P$1_P$1") (pintype "passive"))
      (node (ref "U1") (pin "4") (pinfunction "VDD_4") (pintype "power_in"))
      (node (ref "U2") (pin "4") (pinfunction "VDD_4") (pintype "power_in"))
    )
  )
)
